# CONNECTOR.net
KiCad netlist of a schematic drawn in Altium Designer
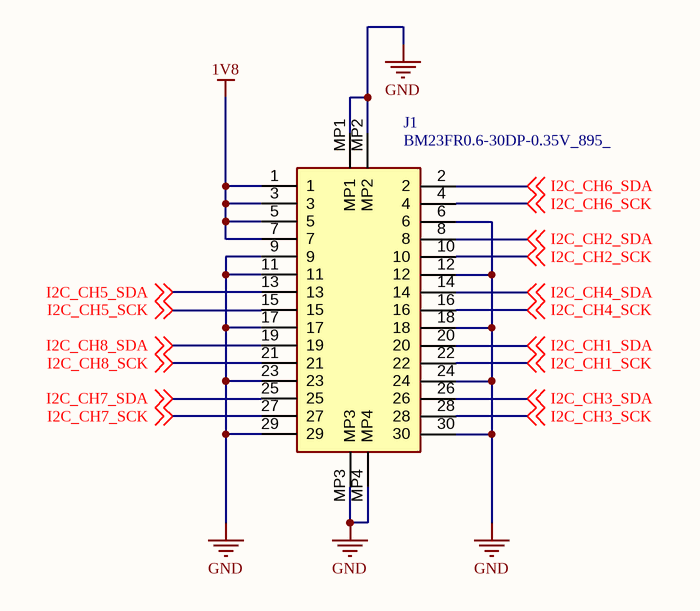
[diagram p0: CONNECTOR.SchDoc]

(export (version "E")
  (design (tool "Eeschema 10.0.6"))
  (components
    (comp (ref "J1")
      (value "BM23FR0.6-30DP-0.35V_895_")
      (footprint "SamacSys:BM23FR0630DP035V895")
      (description "Connector")
      (fields
        (field (name "MANUFACTURER_PART_NUMBER") "BM23FR0.6-30DP-0.35V(895)")
        (field (name "MOUSER PART NUMBER") "798-3FR0630DP035V895")
      )
      (libsource (lib "*") (part "BM23FR0.6-30DP-0.35V_895_"))
    )
  )
  (nets
    (net (code "1") (name "1V8") (class "Default")
      (node (ref "J1") (pin "1") (pinfunction "1_1") (pintype "passive"))
      (node (ref "J1") (pin "3") (pinfunction "3_3") (pintype "passive"))
      (node (ref "J1") (pin "5") (pinfunction "5_5") (pintype "passive"))
      (node (ref "J1") (pin "7") (pinfunction "7_7") (pintype "passive"))
    )
    (net (code "2") (name "GND") (class "Default")
      (node (ref "J1") (pin "11") (pinfunction "11_11") (pintype "passive"))
      (node (ref "J1") (pin "12") (pinfunction "12_12") (pintype "passive"))
      (node (ref "J1") (pin "17") (pinfunction "17_17") (pintype "passive"))
      (node (ref "J1") (pin "18") (pinfunction "18_18") (pintype "passive"))
      (node (ref "J1") (pin "23") (pinfunction "23_23") (pintype "passive"))
      (node (ref "J1") (pin "24") (pinfunction "24_24") (pintype "passive"))
      (node (ref "J1") (pin "29") (pinfunction "29_29") (pintype "passive"))
      (node (ref "J1") (pin "30") (pinfunction "30_30") (pintype "passive"))
      (node (ref "J1") (pin "6") (pinfunction "6_6") (pintype "passive"))
      (node (ref "J1") (pin "9") (pinfunction "9_9") (pintype "passive"))
      (node (ref "J1") (pin "MP1") (pinfunction "MP1_MP1") (pintype "passive"))
      (node (ref "J1") (pin "MP2") (pinfunction "MP2_MP2") (pintype "passive"))
      (node (ref "J1") (pin "MP3") (pinfunction "MP3_MP3") (pintype "passive"))
      (node (ref "J1") (pin "MP4") (pinfunction "MP4_MP4") (pintype "passive"))
    )
    (net (code "3") (name "I2C_CH1_SCK") (class "Default")
      (node (ref "J1") (pin "22") (pinfunction "22_22") (pintype "passive"))
    )
    (net (code "4") (name "I2C_CH1_SDA") (class "Default")
      (node (ref "J1") (pin "20") (pinfunction "20_20") (pintype "passive"))
    )
    (net (code "5") (name "I2C_CH2_SCK") (class "Default")
      (node (ref "J1") (pin "10") (pinfunction "10_10") (pintype "passive"))
    )
    (net (code "6") (name "I2C_CH2_SDA") (class "Default")
      (node (ref "J1") (pin "8") (pinfunction "8_8") (pintype "passive"))
    )
    (net (code "7") (name "I2C_CH3_SCK") (class "Default")
      (node (ref "J1") (pin "28") (pinfunction "28_28") (pintype "passive"))
    )
    (net (code "8") (name "I2C_CH3_SDA") (class "Default")
      (node (ref "J1") (pin "26") (pinfunction "26_26") (pintype "passive"))
    )
    (net (code "9") (name "I2C_CH4_SCK") (class "Default")
      (node (ref "J1") (pin "16") (pinfunction "16_16") (pintype "passive"))
    )
    (net (code "10") (name "I2C_CH4_SDA") (class "Default")
      (node (ref "J1") (pin "14") (pinfunction "14_14") (pintype "passive"))
    )
    (net (code "11") (name "I2C_CH5_SCK") (class "Default")
      (node (ref "J1") (pin "15") (pinfunction "15_15") (pintype "passive"))
    )
    (net (code "12") (name "I2C_CH5_SDA") (class "Default")
      (node (ref "J1") (pin "13") (pinfunction "13_13") (pintype "passive"))
    )
    (net (code "13") (name "I2C_CH6_SCK") (class "Default")
      (node (ref "J1") (pin "4") (pinfunction "4_4") (pintype "passive"))
    )
    (net (code "14") (name "I2C_CH6_SDA") (class "Default")
      (node (ref "J1") (pin "2") (pinfunction "2_2") (pintype "passive"))
    )
    (net (code "15") (name "I2C_CH7_SCK") (class "Default")
      (node (ref "J1") (pin "27") (pinfunction "27_27") (pintype "passive"))
    )
    (net (code "16") (name "I2C_CH7_SDA") (class "Default")
      (node (ref "J1") (pin "25") (pinfunction "25_25") (pintype "passive"))
    )
    (net (code "17") (name "I2C_CH8_SCK") (class "Default")
      (node (ref "J1") (pin "21") (pinfunction "21_21") (pintype "passive"))
    )
    (net (code "18") (name "I2C_CH8_SDA") (class "Default")
      (node (ref "J1") (pin "19") (pinfunction "19_19") (pintype "passive"))
    )
  )
)
